# Midas.net
KiCad netlist of a schematic drawn in Altium Designer
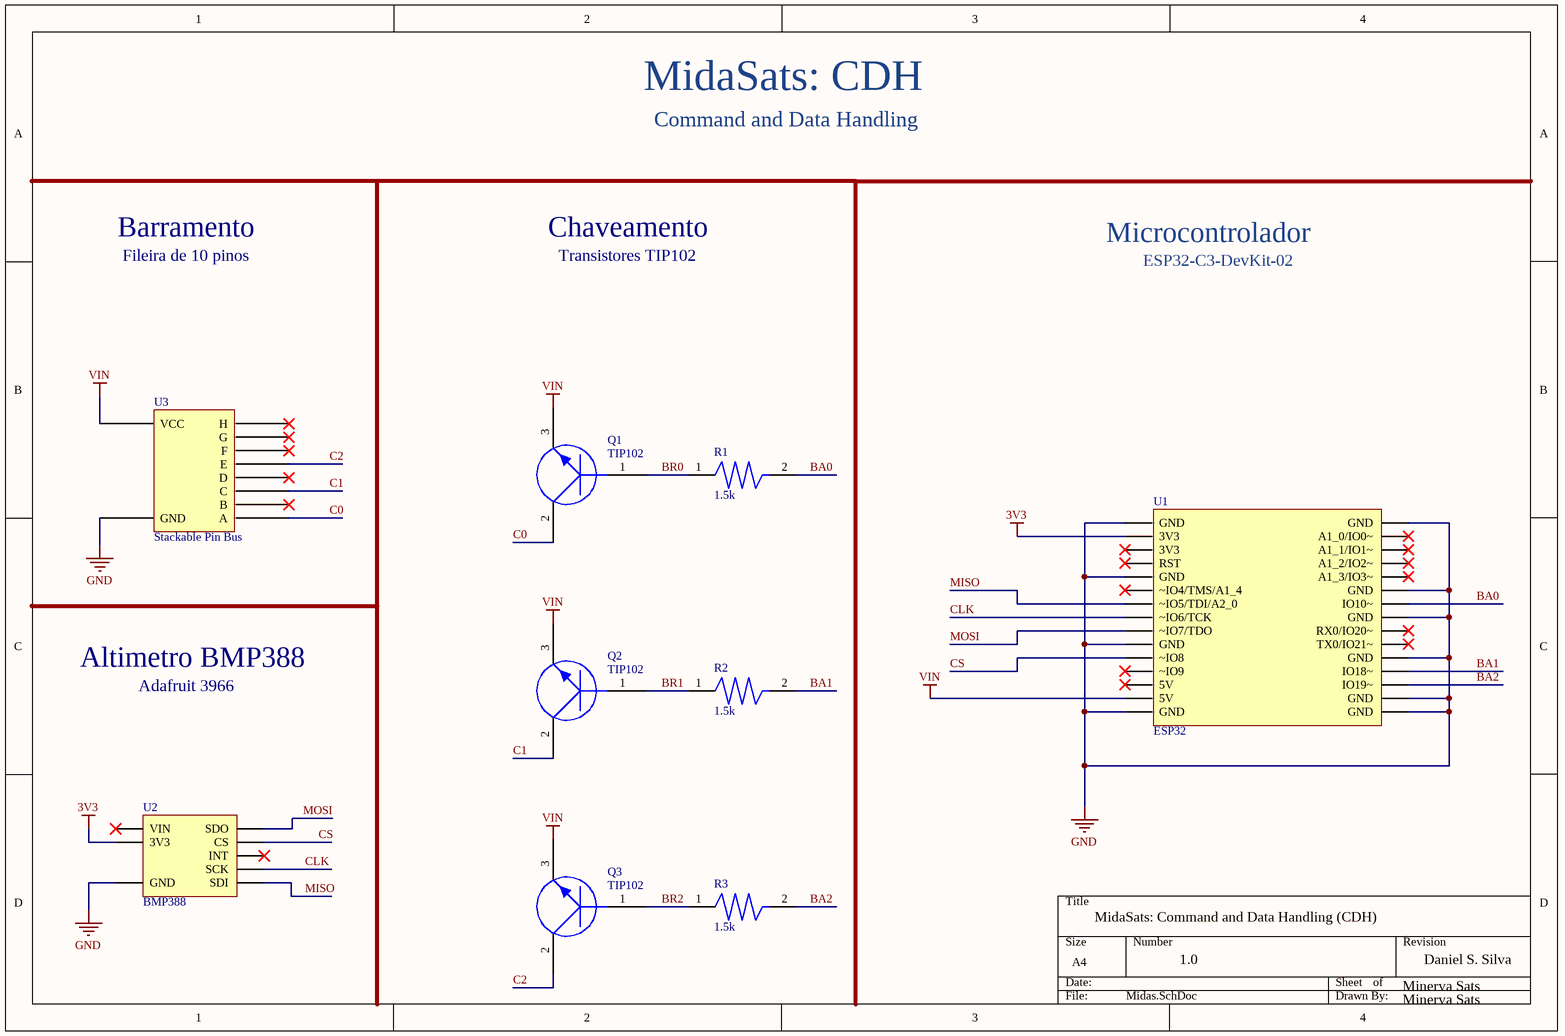
[diagram p0: Midas.SchDoc]

(export (version "E")
  (design (tool "Eeschema 10.0.6"))
  (components
    (comp (ref "Q1")
      (value "TIP102")
      (footprint "ONSC-TO-220-3-221A-09")
      (libsource (lib "Midas") (part "TIP102"))
    )
    (comp (ref "Q2")
      (value "TIP102")
      (footprint "ONSC-TO-220-3-221A-09")
      (libsource (lib "Midas") (part "TIP102"))
    )
    (comp (ref "Q3")
      (value "TIP102")
      (footprint "ONSC-TO-220-3-221A-09")
      (libsource (lib "Midas") (part "TIP102"))
    )
    (comp (ref "R1") (value "1.5k") (footprint "CF18JT1K50") (libsource (lib "Midas") (part "CF18JT1K50")))
    (comp (ref "R2") (value "1.5k") (footprint "CF18JT1K50") (libsource (lib "Midas") (part "CF18JT1K50")))
    (comp (ref "R3") (value "1.5k") (footprint "CF18JT1K50") (libsource (lib "Midas") (part "CF18JT1K50")))
    (comp (ref "U1")
      (value "ESP32")
      (footprint "ESP32")
      (fields
        (field (name "MANUFACTURER") "Espressif Systems")
        (field (name "MANUFACTURER PART NUMBER") "ESP32-C3-DEVKITC-02")
      )
      (libsource (lib "Midas") (part "ESP32-C3-DEVKITC-02"))
    )
    (comp (ref "U2")
      (value "BMP388")
      (footprint "3966")
      (fields
        (field (name "MANUFACTURER") "Adafruit Industries")
        (field (name "MANUFACTURER PART NUMBER") "3966")
      )
      (libsource (lib "Midas") (part "3966"))
    )
    (comp (ref "U3")
      (value "Stackable Pin Bus")
      (footprint "STACKABLE_PIN_BUS")
      (description "10 pinos, Passo 2.54mm, Dimensões da barra 26x2x8mm")
      (libsource (lib "Midas") (part "Barramento Empilhável"))
    )
  )
  (nets
    (net (code "1") (name "/BA0") (class "Default")
      (node (ref "R1") (pin "2") (pintype "passive"))
      (node (ref "U1") (pin "24") (pinfunction "IO10~_24") (pintype "passive"))
    )
    (net (code "2") (name "/BA1") (class "Default")
      (node (ref "R2") (pin "2") (pintype "passive"))
      (node (ref "U1") (pin "19") (pinfunction "IO18~_19") (pintype "passive"))
    )
    (net (code "3") (name "/BA2") (class "Default")
      (node (ref "R3") (pin "2") (pintype "passive"))
      (node (ref "U1") (pin "18") (pinfunction "IO19~_18") (pintype "passive"))
    )
    (net (code "4") (name "/BR0") (class "Default")
      (node (ref "Q1") (pin "1") (pinfunction "B_1") (pintype "passive"))
      (node (ref "R1") (pin "1") (pintype "passive"))
    )
    (net (code "5") (name "/BR1") (class "Default")
      (node (ref "Q2") (pin "1") (pinfunction "B_1") (pintype "passive"))
      (node (ref "R2") (pin "1") (pintype "passive"))
    )
    (net (code "6") (name "/BR2") (class "Default")
      (node (ref "Q3") (pin "1") (pinfunction "B_1") (pintype "passive"))
      (node (ref "R3") (pin "1") (pintype "passive"))
    )
    (net (code "7") (name "/C0") (class "Default")
      (node (ref "Q1") (pin "2") (pinfunction "C_2") (pintype "passive"))
      (node (ref "U3") (pin "3") (pinfunction "A_3") (pintype "passive"))
    )
    (net (code "8") (name "/C1") (class "Default")
      (node (ref "Q2") (pin "2") (pinfunction "C_2") (pintype "passive"))
      (node (ref "U3") (pin "5") (pinfunction "C_5") (pintype "passive"))
    )
    (net (code "9") (name "/C2") (class "Default")
      (node (ref "Q3") (pin "2") (pinfunction "C_2") (pintype "passive"))
      (node (ref "U3") (pin "7") (pinfunction "E_7") (pintype "passive"))
    )
    (net (code "10") (name "/CLK") (class "Default")
      (node (ref "U1") (pin "8") (pinfunction "~IO6/TCK_8") (pintype "passive"))
      (node (ref "U2") (pin "4") (pinfunction "SCK_4") (pintype "passive"))
    )
    (net (code "11") (name "/CS") (class "Default")
      (node (ref "U1") (pin "11") (pinfunction "~IO8_11") (pintype "passive"))
      (node (ref "U2") (pin "7") (pinfunction "CS_7") (pintype "passive"))
    )
    (net (code "12") (name "/MISO") (class "Default")
      (node (ref "U1") (pin "7") (pinfunction "~IO5/TDI/A2_0_7") (pintype "passive"))
      (node (ref "U2") (pin "6") (pinfunction "SDI_6") (pintype "passive"))
    )
    (net (code "13") (name "/MOSI") (class "Default")
      (node (ref "U1") (pin "9") (pinfunction "~IO7/TDO_9") (pintype "passive"))
      (node (ref "U2") (pin "5") (pinfunction "SDO_5") (pintype "passive"))
    )
    (net (code "14") (name "3V3") (class "Default")
      (node (ref "U1") (pin "2") (pinfunction "3V3_2") (pintype "passive"))
      (node (ref "U2") (pin "2") (pinfunction "3V3_2") (pintype "passive"))
    )
    (net (code "15") (name "GND") (class "Default")
      (node (ref "U1") (pin "1") (pinfunction "GND_1") (pintype "passive"))
      (node (ref "U1") (pin "10") (pinfunction "GND_10") (pintype "passive"))
      (node (ref "U1") (pin "15") (pinfunction "GND_15") (pintype "passive"))
      (node (ref "U1") (pin "16") (pinfunction "GND_16") (pintype "passive"))
      (node (ref "U1") (pin "17") (pinfunction "GND_17") (pintype "passive"))
      (node (ref "U1") (pin "20") (pinfunction "GND_20") (pintype "passive"))
      (node (ref "U1") (pin "23") (pinfunction "GND_23") (pintype "passive"))
      (node (ref "U1") (pin "25") (pinfunction "GND_25") (pintype "passive"))
      (node (ref "U1") (pin "30") (pinfunction "GND_30") (pintype "passive"))
      (node (ref "U1") (pin "5") (pinfunction "GND_5") (pintype "passive"))
      (node (ref "U2") (pin "3") (pinfunction "GND_3") (pintype "passive"))
      (node (ref "U3") (pin "2") (pinfunction "GND_2") (pintype "passive"))
    )
    (net (code "16") (name "VIN") (class "Default")
      (node (ref "Q1") (pin "3") (pinfunction "E_3") (pintype "passive"))
      (node (ref "Q2") (pin "3") (pinfunction "E_3") (pintype "passive"))
      (node (ref "Q3") (pin "3") (pinfunction "E_3") (pintype "passive"))
      (node (ref "U1") (pin "14") (pinfunction "5V_14") (pintype "passive"))
      (node (ref "U3") (pin "1") (pinfunction "VCC_1") (pintype "passive"))
    )
    (net (code "17") (name "unconnected-(U1-3V3-Pad3)") (class "Default")
      (node (ref "U1") (pin "3") (pinfunction "3V3_3") (pintype "passive+no_connect"))
    )
    (net (code "18") (name "unconnected-(U1-5V-Pad13)") (class "Default")
      (node (ref "U1") (pin "13") (pinfunction "5V_13") (pintype "passive+no_connect"))
    )
    (net (code "19") (name "unconnected-(U1-A1_0{slash}IO0~-Pad29)") (class "Default")
      (node (ref "U1") (pin "29") (pinfunction "A1_0/IO0~_29") (pintype "passive+no_connect"))
    )
    (net (code "20") (name "unconnected-(U1-A1_1{slash}IO1~-Pad28)") (class "Default")
      (node (ref "U1") (pin "28") (pinfunction "A1_1/IO1~_28") (pintype "passive+no_connect"))
    )
    (net (code "21") (name "unconnected-(U1-A1_2{slash}IO2~-Pad27)") (class "Default")
      (node (ref "U1") (pin "27") (pinfunction "A1_2/IO2~_27") (pintype "passive+no_connect"))
    )
    (net (code "22") (name "unconnected-(U1-A1_3{slash}IO3~-Pad26)") (class "Default")
      (node (ref "U1") (pin "26") (pinfunction "A1_3/IO3~_26") (pintype "passive+no_connect"))
    )
    (net (code "23") (name "unconnected-(U1-RST-Pad4)") (class "Default")
      (node (ref "U1") (pin "4") (pinfunction "RST_4") (pintype "passive+no_connect"))
    )
    (net (code "24") (name "unconnected-(U1-RX0{slash}IO20~-Pad22)") (class "Default")
      (node (ref "U1") (pin "22") (pinfunction "RX0/IO20~_22") (pintype "passive+no_connect"))
    )
    (net (code "25") (name "unconnected-(U1-TX0{slash}IO21~-Pad21)") (class "Default")
      (node (ref "U1") (pin "21") (pinfunction "TX0/IO21~_21") (pintype "passive+no_connect"))
    )
    (net (code "26") (name "unconnected-(U1-~IO4{slash}TMS{slash}A1_4-Pad6)") (class "Default")
      (node (ref "U1") (pin "6") (pinfunction "~IO4/TMS/A1_4_6") (pintype "passive+no_connect"))
    )
    (net (code "27") (name "unconnected-(U1-~IO9-Pad12)") (class "Default")
      (node (ref "U1") (pin "12") (pinfunction "~IO9_12") (pintype "passive+no_connect"))
    )
    (net (code "28") (name "unconnected-(U2-INT-Pad8)") (class "Default")
      (node (ref "U2") (pin "8") (pinfunction "INT_8") (pintype "passive+no_connect"))
    )
    (net (code "29") (name "unconnected-(U2-VIN-Pad1)") (class "Default")
      (node (ref "U2") (pin "1") (pinfunction "VIN_1") (pintype "passive+no_connect"))
    )
    (net (code "30") (name "unconnected-(U3-B-Pad4)") (class "Default")
      (node (ref "U3") (pin "4") (pinfunction "B_4") (pintype "passive+no_connect"))
    )
    (net (code "31") (name "unconnected-(U3-D-Pad6)") (class "Default")
      (node (ref "U3") (pin "6") (pinfunction "D_6") (pintype "passive+no_connect"))
    )
    (net (code "32") (name "unconnected-(U3-F-Pad8)") (class "Default")
      (node (ref "U3") (pin "8") (pinfunction "F_8") (pintype "passive+no_connect"))
    )
    (net (code "33") (name "unconnected-(U3-G-Pad9)") (class "Default")
      (node (ref "U3") (pin "9") (pinfunction "G_9") (pintype "passive+no_connect"))
    )
    (net (code "34") (name "unconnected-(U3-H-Pad10)") (class "Default")
      (node (ref "U3") (pin "10") (pinfunction "H_10") (pintype "passive+no_connect"))
    )
  )
)
